# Precharge_M2019_V1_1.net
KiCad netlist of a schematic drawn in EAGLE
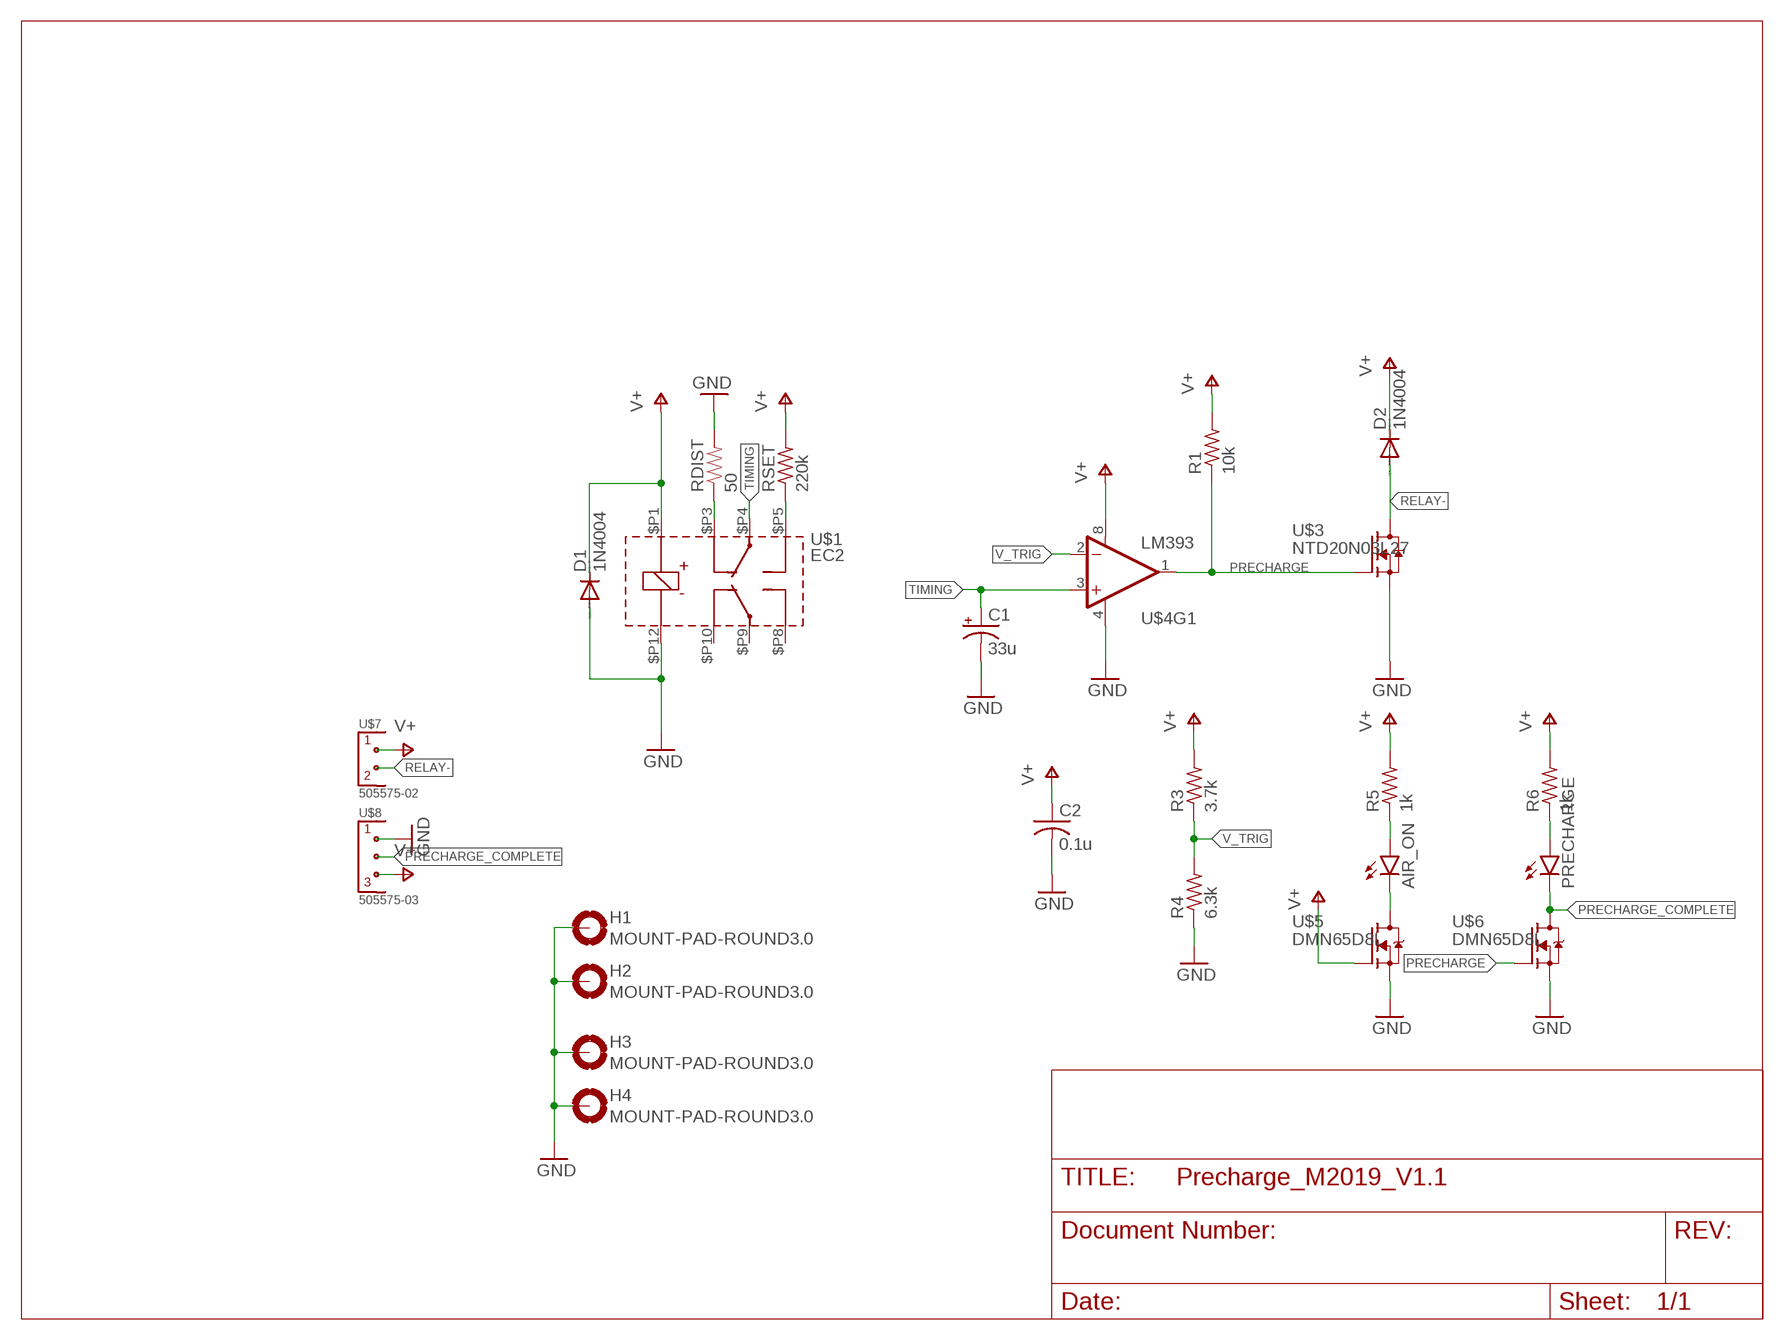
[diagram p0: schematic, sheet 1]

(export (version "E")
  (design (tool "Eeschema 10.0.6"))
  (components
    (comp (ref "AIR_ON")
      (value "LED0603")
      (footprint "eagle-import:LED-0603")
      (libsource (lib "eagle-import") (part "LED0603"))
    )
    (comp (ref "C1")
      (value "33u")
      (footprint "eagle-import:E2,5-5")
      (libsource (lib "eagle-import") (part "CPOL-USE2.5-5"))
    )
    (comp (ref "C2")
      (value "0.1u")
      (footprint "eagle-import:C0805")
      (libsource (lib "eagle-import") (part "C-USC0805"))
    )
    (comp (ref "D1")
      (value "1N4004")
      (footprint "eagle-import:DO41-10")
      (libsource (lib "eagle-import") (part "1N4004"))
    )
    (comp (ref "D2")
      (value "1N4004")
      (footprint "eagle-import:DO41-10")
      (libsource (lib "eagle-import") (part "1N4004"))
    )
    (comp (ref "H1")
      (value "MOUNT-PAD-ROUND3.0")
      (footprint "eagle-import:3,0-PAD")
      (libsource (lib "eagle-import") (part "MOUNT-PAD-ROUND3.0"))
    )
    (comp (ref "H2")
      (value "MOUNT-PAD-ROUND3.0")
      (footprint "eagle-import:3,0-PAD")
      (libsource (lib "eagle-import") (part "MOUNT-PAD-ROUND3.0"))
    )
    (comp (ref "H3")
      (value "MOUNT-PAD-ROUND3.0")
      (footprint "eagle-import:3,0-PAD")
      (libsource (lib "eagle-import") (part "MOUNT-PAD-ROUND3.0"))
    )
    (comp (ref "H4")
      (value "MOUNT-PAD-ROUND3.0")
      (footprint "eagle-import:3,0-PAD")
      (libsource (lib "eagle-import") (part "MOUNT-PAD-ROUND3.0"))
    )
    (comp (ref "PRECHARGE")
      (value "LED0603")
      (footprint "eagle-import:LED-0603")
      (libsource (lib "eagle-import") (part "LED0603"))
    )
    (comp (ref "R1")
      (value "10k")
      (footprint "eagle-import:R0805")
      (libsource (lib "eagle-import") (part "R-US_R0805"))
    )
    (comp (ref "R3")
      (value "3.7k")
      (footprint "eagle-import:R0805")
      (libsource (lib "eagle-import") (part "R-US_R0805"))
    )
    (comp (ref "R4")
      (value "6.3k")
      (footprint "eagle-import:R0805")
      (libsource (lib "eagle-import") (part "R-US_R0805"))
    )
    (comp (ref "R5")
      (value "1k")
      (footprint "eagle-import:R0805")
      (libsource (lib "eagle-import") (part "R-US_R0805"))
    )
    (comp (ref "R6")
      (value "1k")
      (footprint "eagle-import:R0805")
      (libsource (lib "eagle-import") (part "R-US_R0805"))
    )
    (comp (ref "RDIST")
      (value "50")
      (footprint "eagle-import:AXIAL-0.5")
      (libsource (lib "eagle-import") (part "RESISTORPTH-1/2W"))
    )
    (comp (ref "RSET")
      (value "220k")
      (footprint "eagle-import:0207_10")
      (libsource (lib "eagle-import") (part "R-US_0207/10"))
    )
    (comp (ref "U$1")
      (value "EC2")
      (footprint "eagle-import:DPDT_2.54")
      (libsource (lib "eagle-import") (part "EC2"))
    )
    (comp (ref "U$3")
      (value "NTD20N03L27")
      (footprint "eagle-import:DPACK")
      (libsource (lib "eagle-import") (part "NTD20N03L27"))
    )
    (comp (ref "U$4")
      (value "LM393")
      (footprint "eagle-import:SO08")
      (libsource (lib "eagle-import") (part "LM393"))
    )
    (comp (ref "U$5")
      (value "DMN65D8L")
      (footprint "eagle-import:SOT23")
      (libsource (lib "eagle-import") (part "DMN65D8L"))
    )
    (comp (ref "U$6")
      (value "DMN65D8L")
      (footprint "eagle-import:SOT23")
      (libsource (lib "eagle-import") (part "DMN65D8L"))
    )
    (comp (ref "U$7")
      (value "505575-02")
      (footprint "eagle-import:505575-02")
      (libsource (lib "eagle-import") (part "505575-02"))
    )
    (comp (ref "U$8")
      (value "505575-03")
      (footprint "eagle-import:505575-03")
      (libsource (lib "eagle-import") (part "505575-03"))
    )
  )
  (nets
    (net (code "1") (name "GND") (class "Default")
      (node (ref "C1") (pin "-") (pinfunction "-_-") (pintype "passive"))
      (node (ref "C2") (pin "2") (pinfunction "2_2") (pintype "passive"))
      (node (ref "D1") (pin "A") (pinfunction "A_A") (pintype "passive"))
      (node (ref "H1") (pin "B3,0") (pinfunction "MOUNT_B3,0") (pintype "passive"))
      (node (ref "H2") (pin "B3,0") (pinfunction "MOUNT_B3,0") (pintype "passive"))
      (node (ref "H3") (pin "B3,0") (pinfunction "MOUNT_B3,0") (pintype "passive"))
      (node (ref "H4") (pin "B3,0") (pinfunction "MOUNT_B3,0") (pintype "passive"))
      (node (ref "R4") (pin "1") (pinfunction "1_1") (pintype "passive"))
      (node (ref "RDIST") (pin "P$2") (pinfunction "2_P$2") (pintype "passive"))
      (node (ref "U$1") (pin "$P12") (pinfunction "$P12_$P12") (pintype "bidirectional"))
      (node (ref "U$3") (pin "3") (pinfunction "S_3") (pintype "passive"))
      (node (ref "U$4") (pin "4") (pinfunction "V-_4") (pintype "power_in"))
      (node (ref "U$5") (pin "2") (pinfunction "S_2") (pintype "passive"))
      (node (ref "U$6") (pin "2") (pinfunction "S_2") (pintype "passive"))
      (node (ref "U$8") (pin "1") (pinfunction "1_1") (pintype "bidirectional"))
    )
    (net (code "2") (name "Net-(AIR_ON-PadA)") (class "Default")
      (node (ref "AIR_ON") (pin "A") (pinfunction "A_A") (pintype "passive"))
      (node (ref "R5") (pin "1") (pinfunction "1_1") (pintype "passive"))
    )
    (net (code "3") (name "Net-(PRECHARGE-PadA)") (class "Default")
      (node (ref "PRECHARGE") (pin "A") (pinfunction "A_A") (pintype "passive"))
      (node (ref "R6") (pin "1") (pinfunction "1_1") (pintype "passive"))
    )
    (net (code "4") (name "Net-(RDIST-1)") (class "Default")
      (node (ref "RDIST") (pin "P$1") (pinfunction "1_P$1") (pintype "passive"))
      (node (ref "U$1") (pin "$P3") (pinfunction "$P3_$P3") (pintype "passive"))
    )
    (net (code "5") (name "Net-(RSET-Pad1)") (class "Default")
      (node (ref "RSET") (pin "1") (pinfunction "1_1") (pintype "passive"))
      (node (ref "U$1") (pin "$P5") (pinfunction "$P5_$P5") (pintype "passive"))
    )
    (net (code "6") (name "Net-(U$5-D)") (class "Default")
      (node (ref "AIR_ON") (pin "C") (pinfunction "C_C") (pintype "passive"))
      (node (ref "U$5") (pin "3") (pinfunction "D_3") (pintype "passive"))
    )
    (net (code "7") (name "PRECHARGE") (class "Default")
      (node (ref "R1") (pin "1") (pinfunction "1_1") (pintype "passive"))
      (node (ref "U$3") (pin "1") (pinfunction "G_1") (pintype "passive"))
      (node (ref "U$4") (pin "1") (pinfunction "OUT_1") (pintype "output"))
      (node (ref "U$6") (pin "1") (pinfunction "G_1") (pintype "passive"))
    )
    (net (code "8") (name "PRECHARGE_COMPLETE") (class "Default")
      (node (ref "PRECHARGE") (pin "C") (pinfunction "C_C") (pintype "passive"))
      (node (ref "U$6") (pin "3") (pinfunction "D_3") (pintype "passive"))
      (node (ref "U$8") (pin "2") (pinfunction "2_2") (pintype "bidirectional"))
    )
    (net (code "9") (name "RELAY-") (class "Default")
      (node (ref "D2") (pin "A") (pinfunction "A_A") (pintype "passive"))
      (node (ref "U$3") (pin "2") (pinfunction "D_2") (pintype "passive"))
      (node (ref "U$7") (pin "2") (pinfunction "2_2") (pintype "bidirectional"))
    )
    (net (code "10") (name "TIMING") (class "Default")
      (node (ref "C1") (pin "+") (pinfunction "+_+") (pintype "passive"))
      (node (ref "U$1") (pin "$P4") (pinfunction "$P4_$P4") (pintype "passive"))
      (node (ref "U$4") (pin "3") (pinfunction "+IN_3") (pintype "input"))
    )
    (net (code "11") (name "V+") (class "Default")
      (node (ref "C2") (pin "1") (pinfunction "1_1") (pintype "passive"))
      (node (ref "D1") (pin "C") (pinfunction "C_C") (pintype "passive"))
      (node (ref "D2") (pin "C") (pinfunction "C_C") (pintype "passive"))
      (node (ref "R1") (pin "2") (pinfunction "2_2") (pintype "passive"))
      (node (ref "R3") (pin "2") (pinfunction "2_2") (pintype "passive"))
      (node (ref "R5") (pin "2") (pinfunction "2_2") (pintype "passive"))
      (node (ref "R6") (pin "2") (pinfunction "2_2") (pintype "passive"))
      (node (ref "RSET") (pin "2") (pinfunction "2_2") (pintype "passive"))
      (node (ref "U$1") (pin "$P1") (pinfunction "$P1_$P1") (pintype "bidirectional"))
      (node (ref "U$4") (pin "8") (pinfunction "V+_8") (pintype "power_in"))
      (node (ref "U$5") (pin "1") (pinfunction "G_1") (pintype "passive"))
      (node (ref "U$7") (pin "1") (pinfunction "1_1") (pintype "bidirectional"))
      (node (ref "U$8") (pin "3") (pinfunction "3_3") (pintype "bidirectional"))
    )
    (net (code "12") (name "V_TRIG") (class "Default")
      (node (ref "R3") (pin "1") (pinfunction "1_1") (pintype "passive"))
      (node (ref "R4") (pin "2") (pinfunction "2_2") (pintype "passive"))
      (node (ref "U$4") (pin "2") (pinfunction "-IN_2") (pintype "input"))
    )
    (net (code "13") (name "unconnected-(U$1-Pad$P8)") (class "Default")
      (node (ref "U$1") (pin "$P8") (pinfunction "$P8_$P8") (pintype "passive"))
    )
    (net (code "14") (name "unconnected-(U$1-Pad$P9)") (class "Default")
      (node (ref "U$1") (pin "$P9") (pinfunction "$P9_$P9") (pintype "passive"))
    )
    (net (code "15") (name "unconnected-(U$1-Pad$P10)") (class "Default")
      (node (ref "U$1") (pin "$P10") (pinfunction "$P10_$P10") (pintype "passive"))
    )
  )
)
